# TUDSSL_condenar__Hardware_PCBs_PowerModu.net
KiCad netlist of a schematic drawn in Altium Designer
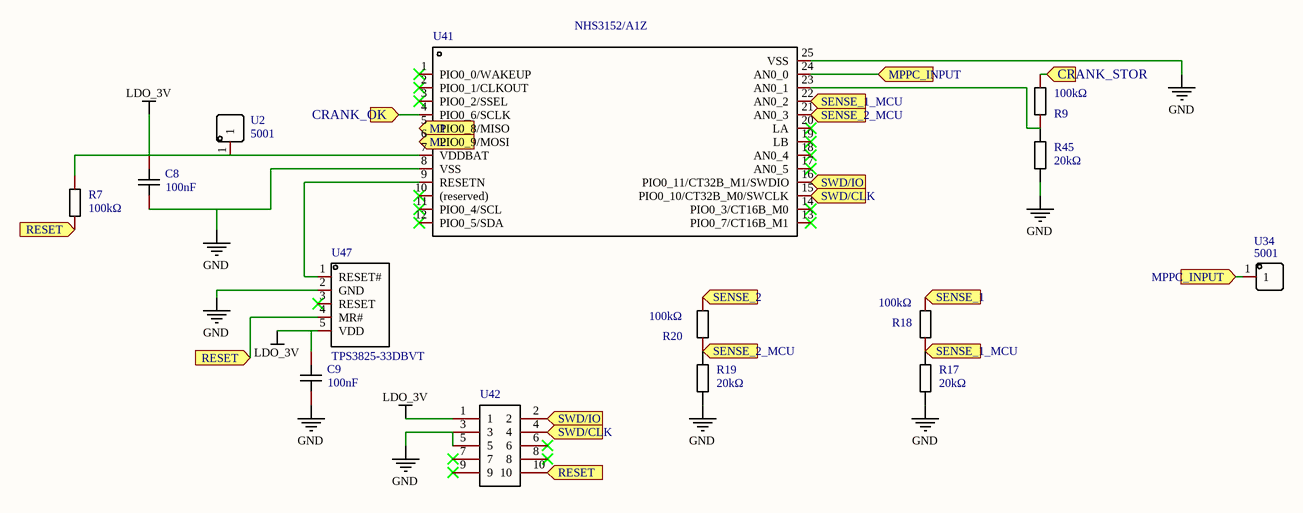
[diagram p0: TUDSSL_condenar__Hardware_PCBs_PowerModules_CrankModuleSMARTEST_TUD-EHC-CrankModule_SMARTEST__2_MCU.schdoc]

(export (version "E")
  (design (tool "Eeschema 10.0.6"))
  (components
    (comp (ref "C8")
      (value "100nF")
      (fields
        (field (name "NAME") "100nF")
        (field (name "MANUFACTURER") "YAGEO")
        (field (name "MANUFACTURER PART") "CC0603KRX7R9BB104")
      )
      (libsource (lib "altium-import") (part "root_3_CC0603KRX7R9BB104_"))
    )
    (comp (ref "C9")
      (value "100nF")
      (fields
        (field (name "NAME") "100nF")
        (field (name "MANUFACTURER") "YAGEO")
        (field (name "MANUFACTURER PART") "CC0603KRX7R9BB104")
      )
      (libsource (lib "altium-import") (part "root_3_CC0603KRX7R9BB104_"))
    )
    (comp (ref "R7")
      (value "100kΩ")
      (fields
        (field (name "MANUFACTURER") "UNI-ROYAL(厚声)")
        (field (name "MANUFACTURER PART") "0603WAF1003T5E")
        (field (name "TOLERANCE") "±1%")
      )
      (libsource (lib "altium-import") (part "root_3_0603WAF1003T5E_"))
    )
    (comp (ref "R9")
      (value "100kΩ")
      (fields
        (field (name "MANUFACTURER") "UNI-ROYAL(厚声)")
        (field (name "MANUFACTURER PART") "0603WAF1003T5E")
        (field (name "TOLERANCE") "±1%")
      )
      (libsource (lib "altium-import") (part "root_1_0603WAF1003T5E_"))
    )
    (comp (ref "R17")
      (value "20kΩ")
      (fields
        (field (name "NAME") "20kΩ")
        (field (name "MANUFACTURER") "UniOhm")
        (field (name "MANUFACTURER PART") "0603WAF2002T5E")
      )
      (libsource (lib "altium-import") (part "root_3_0603WAF2002T5E_"))
    )
    (comp (ref "R18")
      (value "100kΩ")
      (fields
        (field (name "MANUFACTURER") "UNI-ROYAL(厚声)")
        (field (name "MANUFACTURER PART") "0603WAF1003T5E")
        (field (name "TOLERANCE") "±1%")
      )
      (libsource (lib "altium-import") (part "root_1_0603WAF1003T5E_"))
    )
    (comp (ref "R19")
      (value "20kΩ")
      (fields
        (field (name "NAME") "20kΩ")
        (field (name "MANUFACTURER") "UniOhm")
        (field (name "MANUFACTURER PART") "0603WAF2002T5E")
      )
      (libsource (lib "altium-import") (part "root_3_0603WAF2002T5E_"))
    )
    (comp (ref "R20")
      (value "100kΩ")
      (fields
        (field (name "MANUFACTURER") "UNI-ROYAL(厚声)")
        (field (name "MANUFACTURER PART") "0603WAF1003T5E")
        (field (name "TOLERANCE") "±1%")
      )
      (libsource (lib "altium-import") (part "root_1_0603WAF1003T5E_"))
    )
    (comp (ref "R45")
      (value "20kΩ")
      (fields
        (field (name "NAME") "20kΩ")
        (field (name "MANUFACTURER") "UniOhm")
        (field (name "MANUFACTURER PART") "0603WAF2002T5E")
      )
      (libsource (lib "altium-import") (part "root_3_0603WAF2002T5E_"))
    )
    (comp (ref "U2")
      (value "5001")
      (fields (field (name "NAME") "5001") (field (name "MANUFACTURER") "Keystone"))
      (libsource (lib "altium-import") (part "root_1_5001_"))
    )
    (comp (ref "U34")
      (value "5001")
      (fields (field (name "NAME") "5001") (field (name "MANUFACTURER") "Keystone"))
      (libsource (lib "altium-import") (part "root_0_5001_"))
    )
    (comp (ref "U41")
      (value "NHS3152/A1Z")
      (fields (field (name "MANUFACTURER") "NXP(恩智浦)") (field (name "MANUFACTURER PART") "NHS3152/A1Z"))
      (libsource (lib "altium-import") (part "root_0_NHS3152/A1Z_"))
    )
    (comp (ref "U42")
      (value "20021121-00010T4LF")
      (fields (field (name "MANUFACTURER") "Amphenol"))
      (libsource (lib "altium-import") (part "root_3_20021121-00010T4LF_"))
    )
    (comp (ref "U47")
      (value "TPS3825-33DBVT")
      (fields (field (name "MANUFACTURER") "TI(德州仪器)") (field (name "MANUFACTURER PART") "TPS3825-33DBVT"))
      (libsource (lib "altium-import") (part "root_0_TPS3825-33DBVT_"))
    )
  )
  (nets
    (net (code "1") (name "/CRANK_OK") (class "Default")
      (node (ref "U41") (pin "4") (pinfunction "PIO0_6/SCLK_4") (pintype "passive"))
    )
    (net (code "2") (name "/CRANK_STOR") (class "Default")
      (node (ref "R9") (pin "2") (pinfunction "2_2") (pintype "passive"))
    )
    (net (code "3") (name "/M1") (class "Default")
      (node (ref "U41") (pin "5") (pinfunction "PIO0_8/MISO_5") (pintype "passive"))
    )
    (net (code "4") (name "/M2") (class "Default")
      (node (ref "U41") (pin "6") (pinfunction "PIO0_9/MOSI_6") (pintype "passive"))
    )
    (net (code "5") (name "/MPPC_INPUT") (class "Default")
      (node (ref "U34") (pin "1") (pinfunction "1_1") (pintype "passive"))
      (node (ref "U41") (pin "24") (pinfunction "AN0_0_24") (pintype "passive"))
    )
    (net (code "6") (name "/RESET") (class "Default")
      (node (ref "R7") (pin "2") (pinfunction "2_2") (pintype "passive"))
      (node (ref "U42") (pin "10") (pinfunction "10_10") (pintype "passive"))
      (node (ref "U47") (pin "4") (pinfunction "MR#_4") (pintype "passive"))
    )
    (net (code "7") (name "/SENSE_1") (class "Default")
      (node (ref "R18") (pin "2") (pinfunction "2_2") (pintype "passive"))
    )
    (net (code "8") (name "/SENSE_1_MCU") (class "Default")
      (node (ref "R17") (pin "1") (pinfunction "1_1") (pintype "passive"))
      (node (ref "R18") (pin "1") (pinfunction "1_1") (pintype "passive"))
      (node (ref "U41") (pin "22") (pinfunction "AN0_2_22") (pintype "passive"))
    )
    (net (code "9") (name "/SENSE_2") (class "Default")
      (node (ref "R20") (pin "2") (pinfunction "2_2") (pintype "passive"))
    )
    (net (code "10") (name "/SENSE_2_MCU") (class "Default")
      (node (ref "R19") (pin "1") (pinfunction "1_1") (pintype "passive"))
      (node (ref "R20") (pin "1") (pinfunction "1_1") (pintype "passive"))
      (node (ref "U41") (pin "21") (pinfunction "AN0_3_21") (pintype "passive"))
    )
    (net (code "11") (name "/SWD{slash}CLK") (class "Default")
      (node (ref "U41") (pin "15") (pinfunction "PIO0_10/CT32B_M0/SWCLK_15") (pintype "passive"))
      (node (ref "U42") (pin "4") (pinfunction "4_4") (pintype "passive"))
    )
    (net (code "12") (name "/SWD{slash}IO") (class "Default")
      (node (ref "U41") (pin "16") (pinfunction "PIO0_11/CT32B_M1/SWDIO_16") (pintype "passive"))
      (node (ref "U42") (pin "2") (pinfunction "2_2") (pintype "passive"))
    )
    (net (code "13") (name "GND") (class "Default")
      (node (ref "C8") (pin "2") (pinfunction "2_2") (pintype "passive"))
      (node (ref "C9") (pin "2") (pinfunction "2_2") (pintype "passive"))
      (node (ref "R17") (pin "2") (pinfunction "2_2") (pintype "passive"))
      (node (ref "R19") (pin "2") (pinfunction "2_2") (pintype "passive"))
      (node (ref "R45") (pin "2") (pinfunction "2_2") (pintype "passive"))
      (node (ref "U41") (pin "25") (pinfunction "VSS_25") (pintype "passive"))
      (node (ref "U41") (pin "8") (pinfunction "VSS_8") (pintype "passive"))
      (node (ref "U42") (pin "3") (pinfunction "3_3") (pintype "passive"))
      (node (ref "U42") (pin "5") (pinfunction "5_5") (pintype "passive"))
      (node (ref "U47") (pin "2") (pinfunction "GND_2") (pintype "passive"))
    )
    (net (code "14") (name "LDO_3V") (class "Default")
      (node (ref "C8") (pin "1") (pinfunction "1_1") (pintype "passive"))
      (node (ref "C9") (pin "1") (pinfunction "1_1") (pintype "passive"))
      (node (ref "R7") (pin "1") (pinfunction "1_1") (pintype "passive"))
      (node (ref "U2") (pin "1") (pinfunction "1_1") (pintype "passive"))
      (node (ref "U41") (pin "7") (pinfunction "VDDBAT_7") (pintype "passive"))
      (node (ref "U42") (pin "1") (pinfunction "1_1") (pintype "passive"))
      (node (ref "U47") (pin "5") (pinfunction "VDD_5") (pintype "passive"))
    )
    (net (code "15") (name "Net-(U41-AN0_1)") (class "Default")
      (node (ref "R45") (pin "1") (pinfunction "1_1") (pintype "passive"))
      (node (ref "R9") (pin "1") (pinfunction "1_1") (pintype "passive"))
      (node (ref "U41") (pin "23") (pinfunction "AN0_1_23") (pintype "passive"))
    )
    (net (code "16") (name "Net-(U41-RESETN)") (class "Default")
      (node (ref "U41") (pin "9") (pinfunction "RESETN_9") (pintype "passive"))
      (node (ref "U47") (pin "1") (pinfunction "RESET#_1") (pintype "passive"))
    )
    (net (code "17") (name "unconnected-(U41-(reserved)-Pad10)") (class "Default")
      (node (ref "U41") (pin "10") (pinfunction "(reserved)_10") (pintype "passive+no_connect"))
    )
    (net (code "18") (name "unconnected-(U41-AN0_4-Pad18)") (class "Default")
      (node (ref "U41") (pin "18") (pinfunction "AN0_4_18") (pintype "passive+no_connect"))
    )
    (net (code "19") (name "unconnected-(U41-AN0_5-Pad17)") (class "Default")
      (node (ref "U41") (pin "17") (pinfunction "AN0_5_17") (pintype "passive+no_connect"))
    )
    (net (code "20") (name "unconnected-(U41-LA-Pad20)") (class "Default")
      (node (ref "U41") (pin "20") (pinfunction "LA_20") (pintype "passive+no_connect"))
    )
    (net (code "21") (name "unconnected-(U41-LB-Pad19)") (class "Default")
      (node (ref "U41") (pin "19") (pinfunction "LB_19") (pintype "passive+no_connect"))
    )
    (net (code "22") (name "unconnected-(U41-PIO0_0{slash}WAKEUP-Pad1)") (class "Default")
      (node (ref "U41") (pin "1") (pinfunction "PIO0_0/WAKEUP_1") (pintype "passive+no_connect"))
    )
    (net (code "23") (name "unconnected-(U41-PIO0_1{slash}CLKOUT-Pad2)") (class "Default")
      (node (ref "U41") (pin "2") (pinfunction "PIO0_1/CLKOUT_2") (pintype "passive+no_connect"))
    )
    (net (code "24") (name "unconnected-(U41-PIO0_2{slash}SSEL-Pad3)") (class "Default")
      (node (ref "U41") (pin "3") (pinfunction "PIO0_2/SSEL_3") (pintype "passive+no_connect"))
    )
    (net (code "25") (name "unconnected-(U41-PIO0_3{slash}CT16B_M0-Pad14)") (class "Default")
      (node (ref "U41") (pin "14") (pinfunction "PIO0_3/CT16B_M0_14") (pintype "passive+no_connect"))
    )
    (net (code "26") (name "unconnected-(U41-PIO0_4{slash}SCL-Pad11)") (class "Default")
      (node (ref "U41") (pin "11") (pinfunction "PIO0_4/SCL_11") (pintype "passive+no_connect"))
    )
    (net (code "27") (name "unconnected-(U41-PIO0_5{slash}SDA-Pad12)") (class "Default")
      (node (ref "U41") (pin "12") (pinfunction "PIO0_5/SDA_12") (pintype "passive+no_connect"))
    )
    (net (code "28") (name "unconnected-(U41-PIO0_7{slash}CT16B_M1-Pad13)") (class "Default")
      (node (ref "U41") (pin "13") (pinfunction "PIO0_7/CT16B_M1_13") (pintype "passive+no_connect"))
    )
    (net (code "29") (name "unconnected-(U42-Pad6)") (class "Default")
      (node (ref "U42") (pin "6") (pinfunction "6_6") (pintype "passive+no_connect"))
    )
    (net (code "30") (name "unconnected-(U42-Pad7)") (class "Default")
      (node (ref "U42") (pin "7") (pinfunction "7_7") (pintype "passive+no_connect"))
    )
    (net (code "31") (name "unconnected-(U42-Pad8)") (class "Default")
      (node (ref "U42") (pin "8") (pinfunction "8_8") (pintype "passive+no_connect"))
    )
    (net (code "32") (name "unconnected-(U42-Pad9)") (class "Default")
      (node (ref "U42") (pin "9") (pinfunction "9_9") (pintype "passive+no_connect"))
    )
    (net (code "33") (name "unconnected-(U47-RESET-Pad3)") (class "Default")
      (node (ref "U47") (pin "3") (pinfunction "RESET_3") (pintype "passive+no_connect"))
    )
  )
)
